# adapter_board.net
KiCad netlist of a schematic drawn in EAGLE
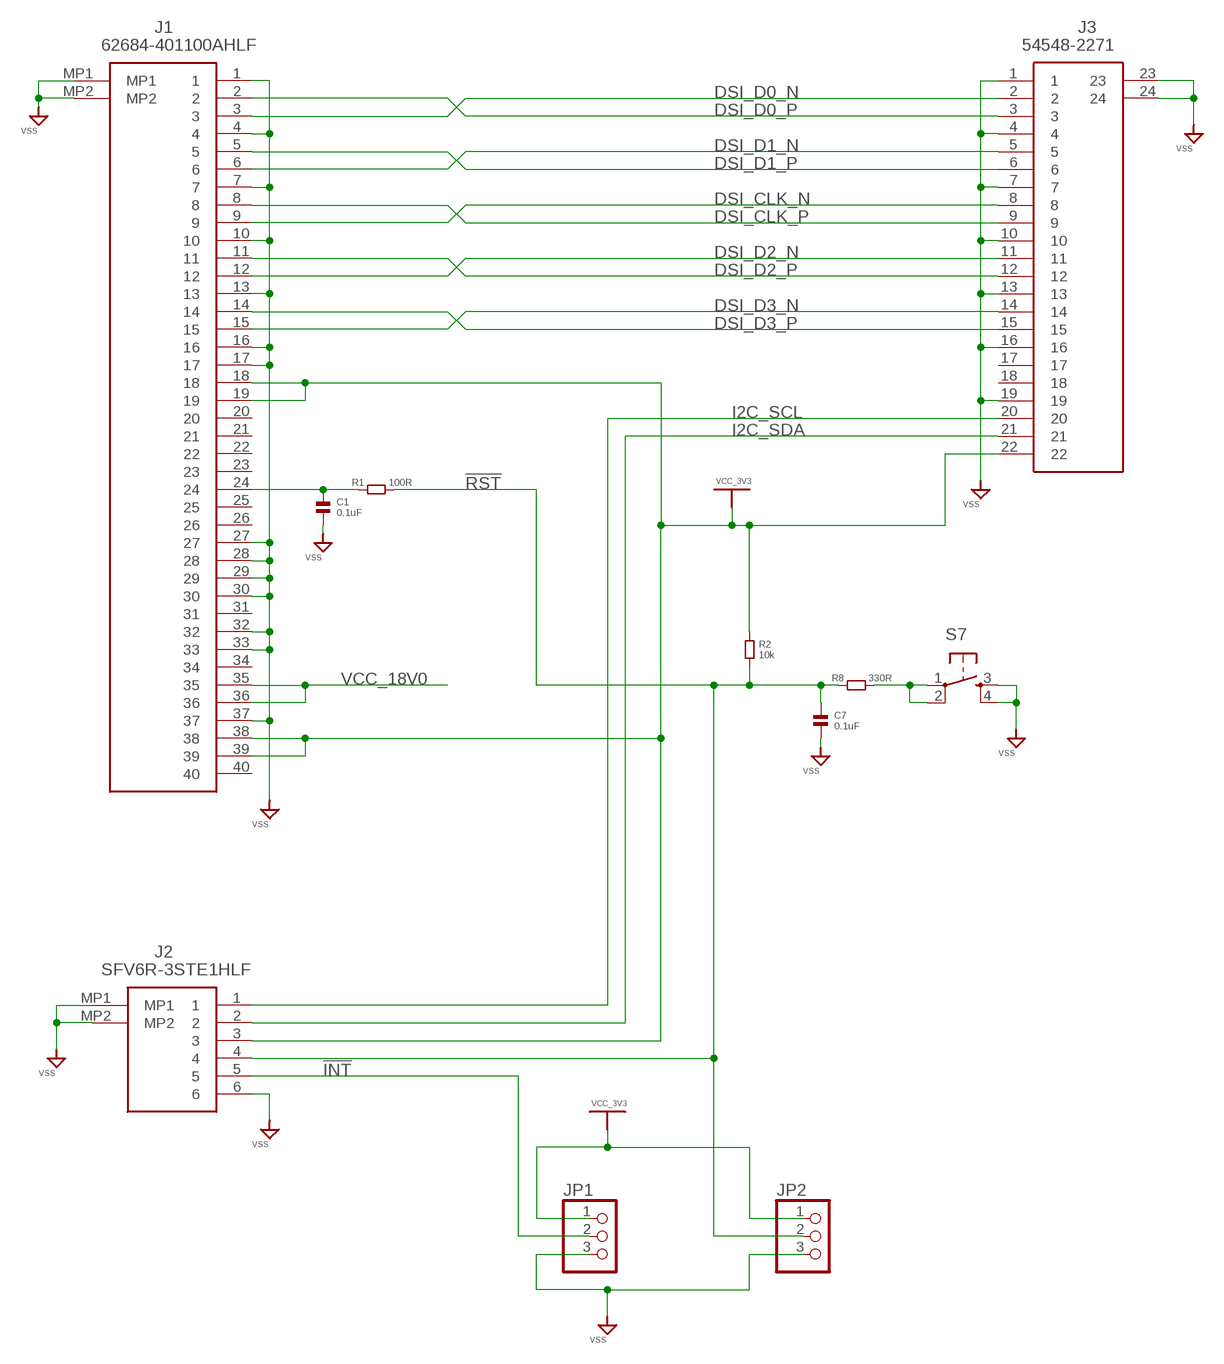
[diagram p0: schematic, sheet 1]
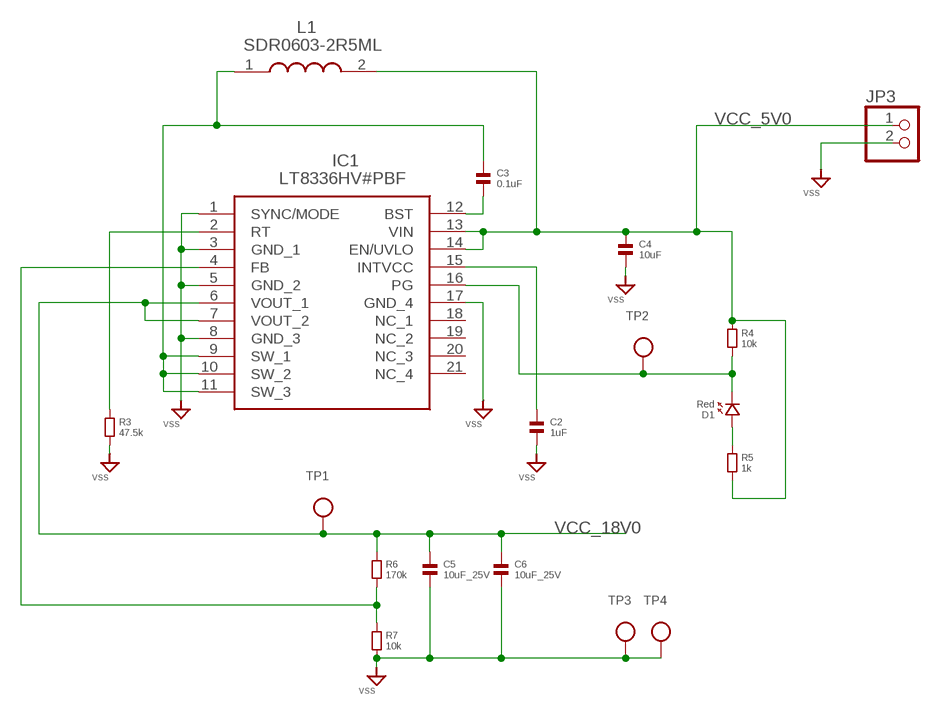
[diagram p1: schematic, sheet 2]

(export (version "E")
  (design (tool "Eeschema 10.0.6"))
  (components
    (comp (ref "C2")
      (value "1uF")
      (footprint "eagle-import:0603")
      (libsource (lib "eagle-import") (part "CAPACITOR.0603"))
    )
    (comp (ref "C3")
      (value "0.1uF")
      (footprint "eagle-import:0603")
      (libsource (lib "eagle-import") (part "CAPACITOR.0603"))
    )
    (comp (ref "C4")
      (value "10uF")
      (footprint "eagle-import:0603")
      (libsource (lib "eagle-import") (part "CAPACITOR.0603"))
    )
    (comp (ref "C5")
      (value "10uF_25V")
      (footprint "eagle-import:0805")
      (libsource (lib "eagle-import") (part "CAPACITOR.0805"))
    )
    (comp (ref "C6")
      (value "10uF_25V")
      (footprint "eagle-import:0805")
      (libsource (lib "eagle-import") (part "CAPACITOR.0805"))
    )
    (comp (ref "D1")
      (value "Red")
      (footprint "eagle-import:0603.LED")
      (libsource (lib "eagle-import") (part "LED.0603"))
    )
    (comp (ref "IC1")
      (value "LT8336HV#PBF")
      (footprint "eagle-import:LT8336HVPBF")
      (fields (field (name "MOUSER_PART_NUMBER") "584-LT8336HV#PBF"))
      (libsource (lib "eagle-import") (part "LT8336HV#PBF"))
    )
    (comp (ref "JP3")
      (value "PINHD-1X2")
      (footprint "eagle-import:1X02")
      (libsource (lib "eagle-import") (part "PINHD-1X2"))
    )
    (comp (ref "L1")
      (value "SDR0603-2R5ML")
      (footprint "eagle-import:SDR06032R5ML")
      (fields (field (name "MOUSER_PART_NUMBER") "652-SDR0603-2R5ML"))
      (libsource (lib "eagle-import") (part "SDR0603-2R5ML"))
    )
    (comp (ref "R3")
      (value "47.5k")
      (footprint "eagle-import:0603")
      (libsource (lib "eagle-import") (part "RESISTOR.0603"))
    )
    (comp (ref "R4")
      (value "10k")
      (footprint "eagle-import:0603")
      (libsource (lib "eagle-import") (part "RESISTOR.0603"))
    )
    (comp (ref "R5")
      (value "1k")
      (footprint "eagle-import:0603")
      (libsource (lib "eagle-import") (part "RESISTOR.0603"))
    )
    (comp (ref "R6")
      (value "170k")
      (footprint "eagle-import:0603")
      (libsource (lib "eagle-import") (part "RESISTOR.0603"))
    )
    (comp (ref "R7")
      (value "10k")
      (footprint "eagle-import:0603")
      (libsource (lib "eagle-import") (part "RESISTOR.0603"))
    )
    (comp (ref "TP1")
      (value "TESTPOINTROUND1MM")
      (footprint "eagle-import:TESTPOINT_ROUND_1MM")
      (libsource (lib "eagle-import") (part "TESTPOINTROUND1MM"))
    )
    (comp (ref "TP2")
      (value "TESTPOINTROUND1MM")
      (footprint "eagle-import:TESTPOINT_ROUND_1MM")
      (libsource (lib "eagle-import") (part "TESTPOINTROUND1MM"))
    )
    (comp (ref "TP3")
      (value "TESTPOINTROUND1MM")
      (footprint "eagle-import:TESTPOINT_ROUND_1MM")
      (libsource (lib "eagle-import") (part "TESTPOINTROUND1MM"))
    )
    (comp (ref "TP4")
      (value "TESTPOINTROUND1MM")
      (footprint "eagle-import:TESTPOINT_ROUND_1MM")
      (libsource (lib "eagle-import") (part "TESTPOINTROUND1MM"))
    )
    (comp (ref "C1")
      (value "0.1uF")
      (footprint "eagle-import:0603")
      (libsource (lib "eagle-import") (part "CAPACITOR.0603"))
    )
    (comp (ref "C7")
      (value "0.1uF")
      (footprint "eagle-import:0603")
      (libsource (lib "eagle-import") (part "CAPACITOR.0603"))
    )
    (comp (ref "J1")
      (value "62684-401100AHLF")
      (footprint "eagle-import:62684401100AHLF")
      (fields (field (name "MOUSER_PART_NUMBER") "649-62684-401100AHLF"))
      (libsource (lib "eagle-import") (part "62684-401100AHLF"))
    )
    (comp (ref "J2")
      (value "SFV6R-3STE1HLF")
      (footprint "eagle-import:SFV6R3STE1HLF")
      (fields (field (name "MOUSER_PART_NUMBER") "649-SFV6R-3STE1HLF"))
      (libsource (lib "eagle-import") (part "SFV6R-3STE1HLF"))
    )
    (comp (ref "J3")
      (value "54548-2271")
      (footprint "eagle-import:545482271")
      (fields (field (name "MOUSER_PART_NUMBER") "538-54548-2271"))
      (libsource (lib "eagle-import") (part "54548-2271"))
    )
    (comp (ref "JP1")
      (value "PINHD-1X3")
      (footprint "eagle-import:1X03")
      (libsource (lib "eagle-import") (part "PINHD-1X3"))
    )
    (comp (ref "JP2")
      (value "PINHD-1X3")
      (footprint "eagle-import:1X03")
      (libsource (lib "eagle-import") (part "PINHD-1X3"))
    )
    (comp (ref "R1")
      (value "100R")
      (footprint "eagle-import:0603")
      (libsource (lib "eagle-import") (part "RESISTOR.0603"))
    )
    (comp (ref "R2")
      (value "10k")
      (footprint "eagle-import:0603")
      (libsource (lib "eagle-import") (part "RESISTOR.0603"))
    )
    (comp (ref "R8")
      (value "330R")
      (footprint "eagle-import:0603")
      (libsource (lib "eagle-import") (part "RESISTOR.0603"))
    )
    (comp (ref "S7")
      (value "TAC_SWITCHPTH")
      (footprint "eagle-import:TACTILE-PTH")
      (libsource (lib "eagle-import") (part "TAC_SWITCHPTH"))
    )
  )
  (nets
    (net (code "1") (name "DSI_CLK_N") (class "Default")
      (node (ref "J1") (pin "9") (pinfunction "9_9") (pintype "bidirectional"))
      (node (ref "J3") (pin "8") (pinfunction "8_8") (pintype "bidirectional"))
    )
    (net (code "2") (name "DSI_CLK_P") (class "Default")
      (node (ref "J1") (pin "8") (pinfunction "8_8") (pintype "bidirectional"))
      (node (ref "J3") (pin "9") (pinfunction "9_9") (pintype "bidirectional"))
    )
    (net (code "3") (name "DSI_D0_N") (class "Default")
      (node (ref "J1") (pin "3") (pinfunction "3_3") (pintype "bidirectional"))
      (node (ref "J3") (pin "2") (pinfunction "2_2") (pintype "bidirectional"))
    )
    (net (code "4") (name "DSI_D0_P") (class "Default")
      (node (ref "J1") (pin "2") (pinfunction "2_2") (pintype "bidirectional"))
      (node (ref "J3") (pin "3") (pinfunction "3_3") (pintype "bidirectional"))
    )
    (net (code "5") (name "DSI_D1_N") (class "Default")
      (node (ref "J1") (pin "6") (pinfunction "6_6") (pintype "bidirectional"))
      (node (ref "J3") (pin "5") (pinfunction "5_5") (pintype "bidirectional"))
    )
    (net (code "6") (name "DSI_D1_P") (class "Default")
      (node (ref "J1") (pin "5") (pinfunction "5_5") (pintype "bidirectional"))
      (node (ref "J3") (pin "6") (pinfunction "6_6") (pintype "bidirectional"))
    )
    (net (code "7") (name "DSI_D2_N") (class "Default")
      (node (ref "J1") (pin "12") (pinfunction "12_12") (pintype "bidirectional"))
      (node (ref "J3") (pin "11") (pinfunction "11_11") (pintype "bidirectional"))
    )
    (net (code "8") (name "DSI_D2_P") (class "Default")
      (node (ref "J1") (pin "11") (pinfunction "11_11") (pintype "bidirectional"))
      (node (ref "J3") (pin "12") (pinfunction "12_12") (pintype "bidirectional"))
    )
    (net (code "9") (name "DSI_D3_N") (class "Default")
      (node (ref "J1") (pin "15") (pinfunction "15_15") (pintype "bidirectional"))
      (node (ref "J3") (pin "14") (pinfunction "14_14") (pintype "bidirectional"))
    )
    (net (code "10") (name "DSI_D3_P") (class "Default")
      (node (ref "J1") (pin "14") (pinfunction "14_14") (pintype "bidirectional"))
      (node (ref "J3") (pin "15") (pinfunction "15_15") (pintype "bidirectional"))
    )
    (net (code "11") (name "I2C_SCL") (class "Default")
      (node (ref "J2") (pin "1") (pinfunction "1_1") (pintype "bidirectional"))
      (node (ref "J3") (pin "20") (pinfunction "20_20") (pintype "bidirectional"))
    )
    (net (code "12") (name "I2C_SDA") (class "Default")
      (node (ref "J2") (pin "2") (pinfunction "2_2") (pintype "bidirectional"))
      (node (ref "J3") (pin "21") (pinfunction "21_21") (pintype "bidirectional"))
    )
    (net (code "13") (name "Net-(C1-Pad1)") (class "Default")
      (node (ref "C1") (pin "1") (pinfunction "1_1") (pintype "bidirectional"))
      (node (ref "J1") (pin "24") (pinfunction "24_24") (pintype "bidirectional"))
      (node (ref "R1") (pin "1") (pinfunction "1_1") (pintype "bidirectional"))
    )
    (net (code "14") (name "Net-(D1-1)") (class "Default")
      (node (ref "D1") (pin "P$1") (pinfunction "1_P$1") (pintype "bidirectional"))
      (node (ref "R5") (pin "1") (pinfunction "1_1") (pintype "bidirectional"))
    )
    (net (code "15") (name "Net-(D1-2)") (class "Default")
      (node (ref "D1") (pin "P$2") (pinfunction "2_P$2") (pintype "bidirectional"))
      (node (ref "IC1") (pin "16") (pinfunction "PG_16") (pintype "bidirectional"))
      (node (ref "R4") (pin "2") (pinfunction "2_2") (pintype "bidirectional"))
      (node (ref "TP2") (pin "P$1") (pinfunction "P$1_P$1") (pintype "bidirectional"))
    )
    (net (code "16") (name "Net-(IC1-BST)") (class "Default")
      (node (ref "C3") (pin "2") (pinfunction "2_2") (pintype "bidirectional"))
      (node (ref "IC1") (pin "12") (pinfunction "BST_12") (pintype "bidirectional"))
    )
    (net (code "17") (name "Net-(IC1-FB)") (class "Default")
      (node (ref "IC1") (pin "4") (pinfunction "FB_4") (pintype "bidirectional"))
      (node (ref "R6") (pin "2") (pinfunction "2_2") (pintype "bidirectional"))
      (node (ref "R7") (pin "1") (pinfunction "1_1") (pintype "bidirectional"))
    )
    (net (code "18") (name "Net-(IC1-INTVCC)") (class "Default")
      (node (ref "C2") (pin "1") (pinfunction "1_1") (pintype "bidirectional"))
      (node (ref "IC1") (pin "15") (pinfunction "INTVCC_15") (pintype "bidirectional"))
    )
    (net (code "19") (name "Net-(IC1-RT)") (class "Default")
      (node (ref "IC1") (pin "2") (pinfunction "RT_2") (pintype "bidirectional"))
      (node (ref "R3") (pin "1") (pinfunction "1_1") (pintype "bidirectional"))
    )
    (net (code "20") (name "Net-(IC1-SW_1)") (class "Default")
      (node (ref "C3") (pin "1") (pinfunction "1_1") (pintype "bidirectional"))
      (node (ref "IC1") (pin "10") (pinfunction "SW_2_10") (pintype "bidirectional"))
      (node (ref "IC1") (pin "11") (pinfunction "SW_3_11") (pintype "bidirectional"))
      (node (ref "IC1") (pin "9") (pinfunction "SW_1_9") (pintype "bidirectional"))
      (node (ref "L1") (pin "1") (pinfunction "1_1") (pintype "bidirectional"))
    )
    (net (code "21") (name "Net-(R8-Pad2)") (class "Default")
      (node (ref "R8") (pin "2") (pinfunction "2_2") (pintype "bidirectional"))
      (node (ref "S7") (pin "1") (pinfunction "1_1") (pintype "passive"))
      (node (ref "S7") (pin "2") (pinfunction "2_2") (pintype "passive"))
    )
    (net (code "22") (name "VCC_3V3") (class "Default")
      (node (ref "J1") (pin "18") (pinfunction "18_18") (pintype "bidirectional"))
      (node (ref "J1") (pin "19") (pinfunction "19_19") (pintype "bidirectional"))
      (node (ref "J1") (pin "38") (pinfunction "38_38") (pintype "bidirectional"))
      (node (ref "J1") (pin "39") (pinfunction "39_39") (pintype "bidirectional"))
      (node (ref "J2") (pin "3") (pinfunction "3_3") (pintype "bidirectional"))
      (node (ref "J3") (pin "22") (pinfunction "22_22") (pintype "bidirectional"))
      (node (ref "JP1") (pin "1") (pinfunction "1_1") (pintype "passive"))
      (node (ref "JP2") (pin "1") (pinfunction "1_1") (pintype "passive"))
      (node (ref "R2") (pin "1") (pinfunction "1_1") (pintype "bidirectional"))
    )
    (net (code "23") (name "VCC_5V0") (class "Default")
      (node (ref "C4") (pin "1") (pinfunction "1_1") (pintype "bidirectional"))
      (node (ref "IC1") (pin "13") (pinfunction "VIN_13") (pintype "bidirectional"))
      (node (ref "IC1") (pin "14") (pinfunction "EN/UVLO_14") (pintype "bidirectional"))
      (node (ref "JP3") (pin "1") (pinfunction "1_1") (pintype "passive"))
      (node (ref "L1") (pin "2") (pinfunction "2_2") (pintype "bidirectional"))
      (node (ref "R4") (pin "1") (pinfunction "1_1") (pintype "bidirectional"))
      (node (ref "R5") (pin "2") (pinfunction "2_2") (pintype "bidirectional"))
    )
    (net (code "24") (name "VCC_18V0") (class "Default")
      (node (ref "C5") (pin "1") (pinfunction "1_1") (pintype "bidirectional"))
      (node (ref "C6") (pin "1") (pinfunction "1_1") (pintype "bidirectional"))
      (node (ref "IC1") (pin "6") (pinfunction "VOUT_1_6") (pintype "bidirectional"))
      (node (ref "IC1") (pin "7") (pinfunction "VOUT_2_7") (pintype "bidirectional"))
      (node (ref "J1") (pin "35") (pinfunction "35_35") (pintype "bidirectional"))
      (node (ref "J1") (pin "36") (pinfunction "36_36") (pintype "bidirectional"))
      (node (ref "R6") (pin "1") (pinfunction "1_1") (pintype "bidirectional"))
      (node (ref "TP1") (pin "P$1") (pinfunction "P$1_P$1") (pintype "bidirectional"))
    )
    (net (code "25") (name "VSS") (class "Default")
      (node (ref "C1") (pin "2") (pinfunction "2_2") (pintype "bidirectional"))
      (node (ref "C2") (pin "2") (pinfunction "2_2") (pintype "bidirectional"))
      (node (ref "C4") (pin "2") (pinfunction "2_2") (pintype "bidirectional"))
      (node (ref "C5") (pin "2") (pinfunction "2_2") (pintype "bidirectional"))
      (node (ref "C6") (pin "2") (pinfunction "2_2") (pintype "bidirectional"))
      (node (ref "C7") (pin "2") (pinfunction "2_2") (pintype "bidirectional"))
      (node (ref "IC1") (pin "1") (pinfunction "SYNC/MODE_1") (pintype "bidirectional"))
      (node (ref "IC1") (pin "17") (pinfunction "GND_4_17") (pintype "bidirectional"))
      (node (ref "IC1") (pin "3") (pinfunction "GND_1_3") (pintype "bidirectional"))
      (node (ref "IC1") (pin "5") (pinfunction "GND_2_5") (pintype "bidirectional"))
      (node (ref "IC1") (pin "8") (pinfunction "GND_3_8") (pintype "bidirectional"))
      (node (ref "J1") (pin "1") (pinfunction "1_1") (pintype "bidirectional"))
      (node (ref "J1") (pin "10") (pinfunction "10_10") (pintype "bidirectional"))
      (node (ref "J1") (pin "13") (pinfunction "13_13") (pintype "bidirectional"))
      (node (ref "J1") (pin "16") (pinfunction "16_16") (pintype "bidirectional"))
      (node (ref "J1") (pin "17") (pinfunction "17_17") (pintype "bidirectional"))
      (node (ref "J1") (pin "27") (pinfunction "27_27") (pintype "bidirectional"))
      (node (ref "J1") (pin "28") (pinfunction "28_28") (pintype "bidirectional"))
      (node (ref "J1") (pin "29") (pinfunction "29_29") (pintype "bidirectional"))
      (node (ref "J1") (pin "30") (pinfunction "30_30") (pintype "bidirectional"))
      (node (ref "J1") (pin "32") (pinfunction "32_32") (pintype "bidirectional"))
      (node (ref "J1") (pin "33") (pinfunction "33_33") (pintype "bidirectional"))
      (node (ref "J1") (pin "37") (pinfunction "37_37") (pintype "bidirectional"))
      (node (ref "J1") (pin "4") (pinfunction "4_4") (pintype "bidirectional"))
      (node (ref "J1") (pin "7") (pinfunction "7_7") (pintype "bidirectional"))
      (node (ref "J1") (pin "MP1") (pinfunction "MP1_MP1") (pintype "bidirectional"))
      (node (ref "J1") (pin "MP2") (pinfunction "MP2_MP2") (pintype "bidirectional"))
      (node (ref "J2") (pin "6") (pinfunction "6_6") (pintype "bidirectional"))
      (node (ref "J2") (pin "MP1") (pinfunction "MP1_MP1") (pintype "bidirectional"))
      (node (ref "J2") (pin "MP2") (pinfunction "MP2_MP2") (pintype "bidirectional"))
      (node (ref "J3") (pin "1") (pinfunction "1_1") (pintype "bidirectional"))
      (node (ref "J3") (pin "10") (pinfunction "10_10") (pintype "bidirectional"))
      (node (ref "J3") (pin "13") (pinfunction "13_13") (pintype "bidirectional"))
      (node (ref "J3") (pin "16") (pinfunction "16_16") (pintype "bidirectional"))
      (node (ref "J3") (pin "19") (pinfunction "19_19") (pintype "bidirectional"))
      (node (ref "J3") (pin "23") (pinfunction "23_23") (pintype "bidirectional"))
      (node (ref "J3") (pin "24") (pinfunction "24_24") (pintype "bidirectional"))
      (node (ref "J3") (pin "4") (pinfunction "4_4") (pintype "bidirectional"))
      (node (ref "J3") (pin "7") (pinfunction "7_7") (pintype "bidirectional"))
      (node (ref "JP1") (pin "3") (pinfunction "3_3") (pintype "passive"))
      (node (ref "JP2") (pin "3") (pinfunction "3_3") (pintype "passive"))
      (node (ref "JP3") (pin "2") (pinfunction "2_2") (pintype "passive"))
      (node (ref "R3") (pin "2") (pinfunction "2_2") (pintype "bidirectional"))
      (node (ref "R7") (pin "2") (pinfunction "2_2") (pintype "bidirectional"))
      (node (ref "S7") (pin "3") (pinfunction "3_3") (pintype "passive"))
      (node (ref "S7") (pin "4") (pinfunction "4_4") (pintype "passive"))
      (node (ref "TP3") (pin "P$1") (pinfunction "P$1_P$1") (pintype "bidirectional"))
      (node (ref "TP4") (pin "P$1") (pinfunction "P$1_P$1") (pintype "bidirectional"))
    )
    (net (code "26") (name "unconnected-(IC1-NC_1-Pad18)") (class "Default")
      (node (ref "IC1") (pin "18") (pinfunction "NC_1_18") (pintype "bidirectional"))
    )
    (net (code "27") (name "unconnected-(IC1-NC_2-Pad19)") (class "Default")
      (node (ref "IC1") (pin "19") (pinfunction "NC_2_19") (pintype "bidirectional"))
    )
    (net (code "28") (name "unconnected-(IC1-NC_3-Pad20)") (class "Default")
      (node (ref "IC1") (pin "20") (pinfunction "NC_3_20") (pintype "bidirectional"))
    )
    (net (code "29") (name "unconnected-(IC1-NC_4-Pad21)") (class "Default")
      (node (ref "IC1") (pin "21") (pinfunction "NC_4_21") (pintype "bidirectional"))
    )
    (net (code "30") (name "unconnected-(J1-Pad20)") (class "Default")
      (node (ref "J1") (pin "20") (pinfunction "20_20") (pintype "bidirectional"))
    )
    (net (code "31") (name "unconnected-(J1-Pad21)") (class "Default")
      (node (ref "J1") (pin "21") (pinfunction "21_21") (pintype "bidirectional"))
    )
    (net (code "32") (name "unconnected-(J1-Pad22)") (class "Default")
      (node (ref "J1") (pin "22") (pinfunction "22_22") (pintype "bidirectional"))
    )
    (net (code "33") (name "unconnected-(J1-Pad23)") (class "Default")
      (node (ref "J1") (pin "23") (pinfunction "23_23") (pintype "bidirectional"))
    )
    (net (code "34") (name "unconnected-(J1-Pad25)") (class "Default")
      (node (ref "J1") (pin "25") (pinfunction "25_25") (pintype "bidirectional"))
    )
    (net (code "35") (name "unconnected-(J1-Pad26)") (class "Default")
      (node (ref "J1") (pin "26") (pinfunction "26_26") (pintype "bidirectional"))
    )
    (net (code "36") (name "unconnected-(J1-Pad31)") (class "Default")
      (node (ref "J1") (pin "31") (pinfunction "31_31") (pintype "bidirectional"))
    )
    (net (code "37") (name "unconnected-(J1-Pad34)") (class "Default")
      (node (ref "J1") (pin "34") (pinfunction "34_34") (pintype "bidirectional"))
    )
    (net (code "38") (name "unconnected-(J1-Pad40)") (class "Default")
      (node (ref "J1") (pin "40") (pinfunction "40_40") (pintype "bidirectional"))
    )
    (net (code "39") (name "unconnected-(J3-Pad17)") (class "Default")
      (node (ref "J3") (pin "17") (pinfunction "17_17") (pintype "bidirectional"))
    )
    (net (code "40") (name "unconnected-(J3-Pad18)") (class "Default")
      (node (ref "J3") (pin "18") (pinfunction "18_18") (pintype "bidirectional"))
    )
    (net (code "41") (name "~{INT}") (class "Default")
      (node (ref "J2") (pin "5") (pinfunction "5_5") (pintype "bidirectional"))
      (node (ref "JP1") (pin "2") (pinfunction "2_2") (pintype "passive"))
    )
    (net (code "42") (name "~{RST}") (class "Default")
      (node (ref "C7") (pin "1") (pinfunction "1_1") (pintype "bidirectional"))
      (node (ref "J2") (pin "4") (pinfunction "4_4") (pintype "bidirectional"))
      (node (ref "JP2") (pin "2") (pinfunction "2_2") (pintype "passive"))
      (node (ref "R1") (pin "2") (pinfunction "2_2") (pintype "bidirectional"))
      (node (ref "R2") (pin "2") (pinfunction "2_2") (pintype "bidirectional"))
      (node (ref "R8") (pin "1") (pinfunction "1_1") (pintype "bidirectional"))
    )
  )
)
